# DC-link.net
KiCad netlist of a schematic drawn in Altium Designer
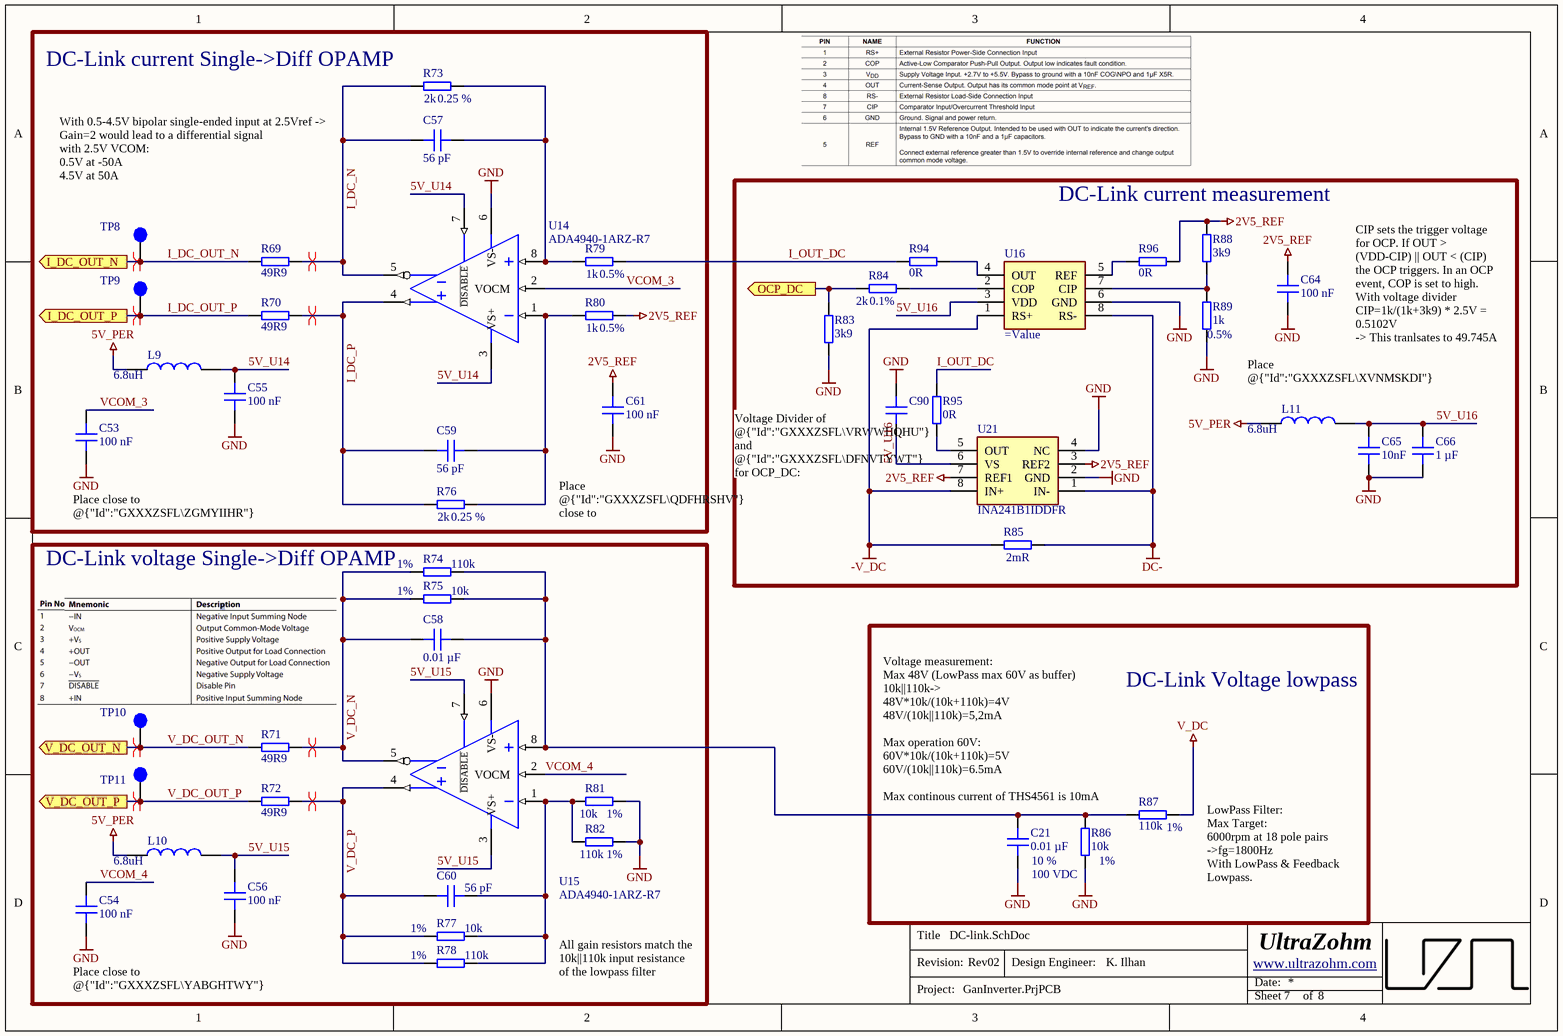
[diagram p0: DC-link.SchDoc]

(export (version "E")
  (design (tool "Eeschema 10.0.6"))
  (components
    (comp (ref "C21")
      (value "0.01 µF")
      (footprint "C_0805")
      (description "100V 10nF 0805 Multilayer Ceramic Capacitors MLCC - SMD/SMT ROHS")
      (fields
        (field (name "MANUFACTURER PART NUMBER") "HV0805X7R103K101NT")
        (field (name "MANUFACTURER") "AIDE")
        (field (name "TOLERANCE") "10 %")
        (field (name "VOLTAGE RATING") "100 VDC")
        (field (name "CREATED FROM") "KIlhan")
      )
      (libsource (lib "user") (part "Capacitor"))
    )
    (comp (ref "C53")
      (value "100 nF")
      (footprint "C_0603")
      (description "Capacitor 0603, 50 VDC, 100 nF, X7R")
      (fields
        (field (name "MANUFACTURER PART NUMBER") "CC0603KRX7R9BB104")
        (field (name "MANUFACTURER") "YAGEO")
        (field (name "CREATED FROM") "AGeiger")
      )
      (libsource (lib "user") (part "Capacitor"))
    )
    (comp (ref "C54")
      (value "100 nF")
      (footprint "C_0603")
      (description "Capacitor 0603, 50 VDC, 100 nF, X7R")
      (fields
        (field (name "MANUFACTURER PART NUMBER") "CC0603KRX7R9BB104")
        (field (name "MANUFACTURER") "YAGEO")
        (field (name "CREATED FROM") "AGeiger")
      )
      (libsource (lib "user") (part "Capacitor"))
    )
    (comp (ref "C55")
      (value "100 nF")
      (footprint "C_0603")
      (description "Capacitor 0603, 50 VDC, 100 nF, X7R")
      (fields
        (field (name "MANUFACTURER PART NUMBER") "CC0603KRX7R9BB104")
        (field (name "MANUFACTURER") "YAGEO")
        (field (name "CREATED FROM") "AGeiger")
      )
      (libsource (lib "user") (part "Capacitor"))
    )
    (comp (ref "C56")
      (value "100 nF")
      (footprint "C_0603")
      (description "Capacitor 0603, 50 VDC, 100 nF, X7R")
      (fields
        (field (name "MANUFACTURER PART NUMBER") "CC0603KRX7R9BB104")
        (field (name "MANUFACTURER") "YAGEO")
        (field (name "CREATED FROM") "AGeiger")
      )
      (libsource (lib "user") (part "Capacitor"))
    )
    (comp (ref "C57")
      (value "56 pF")
      (footprint "C_0603")
      (description "Capacitor 0603, 50 VDC, 56 pF, C0G")
      (fields
        (field (name "MANUFACTURER PART NUMBER") "CL10C560JB8NNNC")
        (field (name "MANUFACTURER") "Samsung Electro-Mechanics")
        (field (name "CREATED FROM") "DHufnagel")
      )
      (libsource (lib "user") (part "Capacitor"))
    )
    (comp (ref "C58")
      (value "0.01 µF")
      (footprint "C_0603")
      (description "25V 10nF C0G ±5% 0603 Multilayer Ceramic Capacitors MLCC - SMD/SMT ROHS")
      (fields
        (field (name "MANUFACTURER PART NUMBER") "C1608C0G1E103JT000N")
        (field (name "MANUFACTURER") "TDK")
        (field (name "CREATED FROM") "KIlhan")
      )
      (libsource (lib "user") (part "Capacitor"))
    )
    (comp (ref "C59")
      (value "56 pF")
      (footprint "C_0603")
      (description "Capacitor 0603, 50 VDC, 56 pF, C0G")
      (fields
        (field (name "MANUFACTURER PART NUMBER") "CL10C560JB8NNNC")
        (field (name "MANUFACTURER") "Samsung Electro-Mechanics")
        (field (name "CREATED FROM") "DHufnagel")
      )
      (libsource (lib "user") (part "Capacitor"))
    )
    (comp (ref "C60")
      (value "56 pF")
      (footprint "C_0603")
      (description "Capacitor 0603, 50 VDC, 56 pF, C0G")
      (fields
        (field (name "MANUFACTURER PART NUMBER") "CL10C560JB8NNNC")
        (field (name "MANUFACTURER") "Samsung Electro-Mechanics")
        (field (name "CREATED FROM") "DHufnagel")
      )
      (libsource (lib "user") (part "Capacitor"))
    )
    (comp (ref "C61")
      (value "100 nF")
      (footprint "C_0603")
      (description "Capacitor 0603, 50 VDC, 100 nF, X7R")
      (fields
        (field (name "MANUFACTURER PART NUMBER") "CC0603KRX7R9BB104")
        (field (name "MANUFACTURER") "YAGEO")
        (field (name "CREATED FROM") "AGeiger")
      )
      (libsource (lib "user") (part "Capacitor"))
    )
    (comp (ref "C64")
      (value "100 nF")
      (footprint "C_0603")
      (description "Capacitor 0603, 50 VDC, 100 nF, X7R")
      (fields
        (field (name "MANUFACTURER PART NUMBER") "CC0603KRX7R9BB104")
        (field (name "MANUFACTURER") "YAGEO")
        (field (name "CREATED FROM") "AGeiger")
      )
      (libsource (lib "user") (part "Capacitor"))
    )
    (comp (ref "C65")
      (value "10nF")
      (footprint "C_0603")
      (description "50V 10nF 2X1 ±10%")
      (fields
        (field (name "MANUFACTURER PART NUMBER") "CT41G-0603-2X1-50V-0.01μF-K(N)")
        (field (name "MANUFACTURER") "TORCH")
        (field (name "CREATED FROM") "KIlhan")
      )
      (libsource (lib "user") (part "Capacitor"))
    )
    (comp (ref "C66")
      (value "1 µF")
      (footprint "C_0603")
      (description "50V 1uF X7R ±10% 0603 Multilayer Ceramic Capacitors MLCC - SMD/SMT ROHS")
      (fields
        (field (name "MANUFACTURER PART NUMBER") "UMK107AB7105KA-T")
        (field (name "MANUFACTURER") "Taiyo Yuden")
        (field (name "CREATED FROM") "NDiringer")
      )
      (libsource (lib "user") (part "Capacitor"))
    )
    (comp (ref "C90")
      (value "100 nF")
      (footprint "C_0603")
      (description "Capacitor 0603, 50 VDC, 100 nF, X7R")
      (fields
        (field (name "MANUFACTURER PART NUMBER") "CC0603KRX7R9BB104")
        (field (name "MANUFACTURER") "YAGEO")
        (field (name "CREATED FROM") "AGeiger")
      )
      (libsource (lib "user") (part "Capacitor"))
    )
    (comp (ref "L9")
      (value "6.8uH")
      (footprint "INDC1608X95N")
      (description "6.8uH ±10% 0603 Inductors (SMD) ROHS")
      (fields
        (field (name "MF") "EPCOS / TDK")
        (field (name "MPN") "B82464G4154M")
        (field (name "CREATED FROM") "KIlhan")
      )
      (libsource (lib "user") (part "B82464G4154M"))
    )
    (comp (ref "L10")
      (value "6.8uH")
      (footprint "INDC1608X95N")
      (description "6.8uH ±10% 0603 Inductors (SMD) ROHS")
      (fields
        (field (name "MF") "EPCOS / TDK")
        (field (name "MPN") "B82464G4154M")
        (field (name "CREATED FROM") "KIlhan")
      )
      (libsource (lib "user") (part "B82464G4154M"))
    )
    (comp (ref "L11")
      (value "6.8uH")
      (footprint "INDC1608X95N")
      (description "6.8uH ±10% 0603 Inductors (SMD) ROHS")
      (fields
        (field (name "MF") "EPCOS / TDK")
        (field (name "MPN") "B82464G4154M")
        (field (name "CREATED FROM") "KIlhan")
      )
      (libsource (lib "user") (part "B82464G4154M"))
    )
    (comp (ref "R69")
      (value "49R9")
      (footprint "RES 0603_1608")
      (description "125mW Thin Film Resistor ±0.1% ±25ppm/℃ 49.9Ω 0603")
      (fields
        (field (name "MANUFACTURER PART NUMBER") "TNPW060349R9BEEA")
        (field (name "MANUFACTURER") "Vishay Intertech")
        (field (name "CREATED FROM") "KIlhan")
      )
      (libsource (lib "user") (part "Resistor"))
    )
    (comp (ref "R70")
      (value "49R9")
      (footprint "RES 0603_1608")
      (description "125mW Thin Film Resistor ±0.1% ±25ppm/℃ 49.9Ω 0603")
      (fields
        (field (name "MANUFACTURER PART NUMBER") "TNPW060349R9BEEA")
        (field (name "MANUFACTURER") "Vishay Intertech")
        (field (name "CREATED FROM") "KIlhan")
      )
      (libsource (lib "user") (part "Resistor"))
    )
    (comp (ref "R71")
      (value "49R9")
      (footprint "RES 0603_1608")
      (description "125mW Thin Film Resistor ±0.1% ±25ppm/℃ 49.9Ω 0603")
      (fields
        (field (name "MANUFACTURER PART NUMBER") "TNPW060349R9BEEA")
        (field (name "MANUFACTURER") "Vishay Intertech")
        (field (name "CREATED FROM") "KIlhan")
      )
      (libsource (lib "user") (part "Resistor"))
    )
    (comp (ref "R72")
      (value "49R9")
      (footprint "RES 0603_1608")
      (description "125mW Thin Film Resistor ±0.1% ±25ppm/℃ 49.9Ω 0603")
      (fields
        (field (name "MANUFACTURER PART NUMBER") "TNPW060349R9BEEA")
        (field (name "MANUFACTURER") "Vishay Intertech")
        (field (name "CREATED FROM") "KIlhan")
      )
      (libsource (lib "user") (part "Resistor"))
    )
    (comp (ref "R73")
      (value "2k")
      (footprint "RES 0603_1608")
      (description "100mW Thin Film Resistor ±50ppm/℃ ±0.25% 2kΩ 0603 Chip Resistor - Surface Mount ROHS")
      (fields
        (field (name "MANUFACTURER PART NUMBER") "RT0603CRE072KL")
        (field (name "MANUFACTURER") "YAGEO")
        (field (name "TOLERANCE") "0.25 %")
        (field (name "CREATED FROM") "KIlhan")
      )
      (libsource (lib "user") (part "Resistor"))
    )
    (comp (ref "R74")
      (value "110k")
      (footprint "RES 0603_1608")
      (description "100mW Thick Film Resistors ±100ppm/℃ ±1% 110kΩ 0603 Chip Resistor - Surface Mount ROHS")
      (fields
        (field (name "MANUFACTURER PART NUMBER") "WR06X1103FTL")
        (field (name "MANUFACTURER") "Walsin Tech Corp")
        (field (name "TOLERANCE") "1%")
        (field (name "CREATED FROM") "KIlhan")
      )
      (libsource (lib "user") (part "Resistor"))
    )
    (comp (ref "R75")
      (value "10k")
      (footprint "RES 0603_1608")
      (description "SMD resistor 1%")
      (fields
        (field (name "MANUFACTURER PART NUMBER") "0603WAF1002T5E")
        (field (name "MANUFACTURER") "UNI-ROYAL")
        (field (name "TOLERANCE") "1%")
        (field (name "CREATED FROM") "AGeiger")
      )
      (libsource (lib "user") (part "Resistor"))
    )
    (comp (ref "R76")
      (value "2k")
      (footprint "RES 0603_1608")
      (description "100mW Thin Film Resistor ±50ppm/℃ ±0.25% 2kΩ 0603 Chip Resistor - Surface Mount ROHS")
      (fields
        (field (name "MANUFACTURER PART NUMBER") "RT0603CRE072KL")
        (field (name "MANUFACTURER") "YAGEO")
        (field (name "TOLERANCE") "0.25 %")
        (field (name "CREATED FROM") "KIlhan")
      )
      (libsource (lib "user") (part "Resistor"))
    )
    (comp (ref "R77")
      (value "10k")
      (footprint "RES 0603_1608")
      (description "SMD resistor 1%")
      (fields
        (field (name "MANUFACTURER PART NUMBER") "0603WAF1002T5E")
        (field (name "MANUFACTURER") "UNI-ROYAL")
        (field (name "TOLERANCE") "1%")
        (field (name "CREATED FROM") "AGeiger")
      )
      (libsource (lib "user") (part "Resistor"))
    )
    (comp (ref "R78")
      (value "110k")
      (footprint "RES 0603_1608")
      (description "100mW Thick Film Resistors ±100ppm/℃ ±1% 110kΩ 0603 Chip Resistor - Surface Mount ROHS")
      (fields
        (field (name "MANUFACTURER PART NUMBER") "WR06X1103FTL")
        (field (name "MANUFACTURER") "Walsin Tech Corp")
        (field (name "TOLERANCE") "1%")
        (field (name "CREATED FROM") "KIlhan")
      )
      (libsource (lib "user") (part "Resistor"))
    )
    (comp (ref "R79")
      (value "1k")
      (footprint "RES 0603_1608")
      (description "SMD resistor E24 series 470 kOhms 100-200 mW 0603 1%")
      (fields
        (field (name "MANUFACTURER PART NUMBER") "0603WAD1001T5E")
        (field (name "MANUFACTURER") "UNI-ROYAL(Uniroyal Elec)")
        (field (name "TOLERANCE") "0.5%")
        (field (name "CREATED FROM") "NDiringer")
      )
      (libsource (lib "user") (part "Resistor"))
    )
    (comp (ref "R80")
      (value "1k")
      (footprint "RES 0603_1608")
      (description "SMD resistor E24 series 470 kOhms 100-200 mW 0603 1%")
      (fields
        (field (name "MANUFACTURER PART NUMBER") "0603WAD1001T5E")
        (field (name "MANUFACTURER") "UNI-ROYAL(Uniroyal Elec)")
        (field (name "TOLERANCE") "0.5%")
        (field (name "CREATED FROM") "NDiringer")
      )
      (libsource (lib "user") (part "Resistor"))
    )
    (comp (ref "R81")
      (value "10k")
      (footprint "RES 0603_1608")
      (description "SMD resistor 1%")
      (fields
        (field (name "MANUFACTURER PART NUMBER") "0603WAF1002T5E")
        (field (name "MANUFACTURER") "UNI-ROYAL")
        (field (name "TOLERANCE") "1%")
        (field (name "CREATED FROM") "AGeiger")
      )
      (libsource (lib "user") (part "Resistor"))
    )
    (comp (ref "R82")
      (value "110k")
      (footprint "RES 0603_1608")
      (description "100mW Thick Film Resistors ±100ppm/℃ ±1% 110kΩ 0603 Chip Resistor - Surface Mount ROHS")
      (fields
        (field (name "MANUFACTURER PART NUMBER") "WR06X1103FTL")
        (field (name "MANUFACTURER") "Walsin Tech Corp")
        (field (name "TOLERANCE") "1%")
        (field (name "CREATED FROM") "KIlhan")
      )
      (libsource (lib "user") (part "Resistor"))
    )
    (comp (ref "R83")
      (value "3k9")
      (footprint "RES 0603_1608")
      (description "SMD resistor E24 series")
      (fields
        (field (name "MANUFACTURER PART NUMBER") "RT0603FRE073K9L")
        (field (name "MANUFACTURER") "YAGEO")
        (field (name "CREATED FROM") "DHufnagel")
      )
      (libsource (lib "user") (part "Resistor"))
    )
    (comp (ref "R84")
      (value "2k")
      (footprint "RES 0603_1608")
      (description "SMD resistor 0.1%")
      (fields
        (field (name "MANUFACTURER PART NUMBER") "ERJ-PB3B2001V")
        (field (name "MANUFACTURER") "Panasonic")
        (field (name "TOLERANCE") "0.1%")
        (field (name "CREATED FROM") "DHufnagel")
      )
      (libsource (lib "user") (part "Resistor"))
    )
    (comp (ref "R85")
      (value "2mR")
      (footprint "3921")
      (description "Shunt resistor 2mOhm, 5W, 1%")
      (fields
        (field (name "MANUFACTURER PART NUMBER") "PU3921FKMP50R002L")
        (field (name "MANUFACTURER") "YAGEO")
        (field (name "CREATED FROM") "DHufnagel")
      )
      (libsource (lib "user") (part "Resistor"))
    )
    (comp (ref "R86")
      (value "10k")
      (footprint "RES 0603_1608")
      (description "SMD resistor 1%")
      (fields
        (field (name "MANUFACTURER PART NUMBER") "0603WAF1002T5E")
        (field (name "MANUFACTURER") "UNI-ROYAL")
        (field (name "TOLERANCE") "1%")
        (field (name "CREATED FROM") "AGeiger")
      )
      (libsource (lib "user") (part "Resistor"))
    )
    (comp (ref "R87")
      (value "110k")
      (footprint "RES 0603_1608")
      (description "100mW Thick Film Resistors ±100ppm/℃ ±1% 110kΩ 0603 Chip Resistor - Surface Mount ROHS")
      (fields
        (field (name "MANUFACTURER PART NUMBER") "WR06X1103FTL")
        (field (name "MANUFACTURER") "Walsin Tech Corp")
        (field (name "TOLERANCE") "1%")
        (field (name "CREATED FROM") "KIlhan")
      )
      (libsource (lib "user") (part "Resistor"))
    )
    (comp (ref "R88")
      (value "3k9")
      (footprint "RES 0603_1608")
      (description "SMD resistor E24 series")
      (fields
        (field (name "MANUFACTURER PART NUMBER") "RT0603FRE073K9L")
        (field (name "MANUFACTURER") "YAGEO")
        (field (name "CREATED FROM") "DHufnagel")
      )
      (libsource (lib "user") (part "Resistor"))
    )
    (comp (ref "R89")
      (value "1k")
      (footprint "RES 0603_1608")
      (description "SMD resistor E24 series 470 kOhms 100-200 mW 0603 1%")
      (fields
        (field (name "MANUFACTURER PART NUMBER") "0603WAD1001T5E")
        (field (name "MANUFACTURER") "UNI-ROYAL(Uniroyal Elec)")
        (field (name "TOLERANCE") "0.5%")
        (field (name "CREATED FROM") "NDiringer")
      )
      (libsource (lib "user") (part "Resistor"))
    )
    (comp (ref "R94")
      (value "0R")
      (footprint "RES 0603_1608")
      (description "SMD resistor E24 series")
      (fields
        (field (name "MANUFACTURER PART NUMBER") "RC0603JR-070RL")
        (field (name "MANUFACTURER") "YAGEO")
        (field (name "CREATED FROM") "MGremer")
      )
      (libsource (lib "user") (part "Resistor"))
    )
    (comp (ref "R95")
      (value "0R")
      (footprint "RES 0603_1608")
      (description "SMD resistor E24 series")
      (fields
        (field (name "MANUFACTURER PART NUMBER") "RC0603JR-070RL")
        (field (name "MANUFACTURER") "YAGEO")
        (field (name "CREATED FROM") "MGremer")
      )
      (libsource (lib "user") (part "Resistor"))
    )
    (comp (ref "R96")
      (value "0R")
      (footprint "RES 0603_1608")
      (description "SMD resistor E24 series")
      (fields
        (field (name "MANUFACTURER PART NUMBER") "RC0603JR-070RL")
        (field (name "MANUFACTURER") "YAGEO")
        (field (name "CREATED FROM") "MGremer")
      )
      (libsource (lib "user") (part "Resistor"))
    )
    (comp (ref "TP8")
      (value "Testpoint 1mm")
      (footprint "TP_1mm")
      (fields
        (field (name "MANUFACTURER PART NUMBER") "NULL")
        (field (name "CREATED") "2018_06_25_AGeiger")
        (field (name "CREATED FROM") "AGeiger")
      )
      (libsource (lib "user") (part "TP_1mm"))
    )
    (comp (ref "TP9")
      (value "Testpoint 1mm")
      (footprint "TP_1mm")
      (fields
        (field (name "MANUFACTURER PART NUMBER") "NULL")
        (field (name "CREATED") "2018_06_25_AGeiger")
        (field (name "CREATED FROM") "AGeiger")
      )
      (libsource (lib "user") (part "TP_1mm"))
    )
    (comp (ref "TP10")
      (value "Testpoint 1mm")
      (footprint "TP_1mm")
      (fields
        (field (name "MANUFACTURER PART NUMBER") "NULL")
        (field (name "CREATED") "2018_06_25_AGeiger")
        (field (name "CREATED FROM") "AGeiger")
      )
      (libsource (lib "user") (part "TP_1mm"))
    )
    (comp (ref "TP11")
      (value "Testpoint 1mm")
      (footprint "TP_1mm")
      (fields
        (field (name "MANUFACTURER PART NUMBER") "NULL")
        (field (name "CREATED") "2018_06_25_AGeiger")
        (field (name "CREATED FROM") "AGeiger")
      )
      (libsource (lib "user") (part "TP_1mm"))
    )
    (comp (ref "U14")
      (value "ADA4940-1ARZ-R7")
      (footprint "SOT127P600X175-8N")
      (description "Fully Differential Amplifier, Ultralow-Power,Low Distortion, 260-MHz")
      (fields
        (field (name "MANUFACTURER") "Analog Devices")
        (field (name "LCSC PART NUMBER") "C730049")
        (field (name "CREATED FROM") "DHufnagel")
      )
      (libsource (lib "user") (part "ADA4940-1ARZ"))
    )
    (comp (ref "U15")
      (value "ADA4940-1ARZ-R7")
      (footprint "SOT127P600X175-8N")
      (description "Fully Differential Amplifier, Ultralow-Power,Low Distortion, 260-MHz")
      (fields
        (field (name "MANUFACTURER") "Analog Devices")
        (field (name "LCSC PART NUMBER") "C730049")
        (field (name "CREATED FROM") "DHufnagel")
      )
      (libsource (lib "user") (part "ADA4940-1ARZ"))
    )
    (comp (ref "U16")
      (value "~")
      (footprint "SOP65P490X110-8N")
      (description "Current Sense Amplifier, 300kHz, -0.1V to 65V CMV, 2 Channel")
      (fields
        (field (name "MANUFACTURER_PART_NUMBER") "MAX40056TAUA+")
        (field (name "MOUSER PART NUMBER") "700-MAX40056TAUA+")
        (field (name "CREATED FROM") "KIlhan")
      )
      (libsource (lib "user") (part "MAX40056TAUA+"))
    )
    (comp (ref "U21")
      (value "INA241B1IDDFR")
      (footprint "SOT65P280X110-8N")
      (fields
        (field (name "MOUSER PART NUMBER") "595-INA241B1IDDFR")
        (field (name "LCSC PART NUMBER") "C7433256")
        (field (name "MANUFACTURER") "Texas Instruments")
        (field (name "CREATED FROM") "KIlhan")
      )
      (libsource (lib "user") (part "INA241B1IDDFR"))
    )
  )
  (nets
    (net (code "1") (name "-V_DC") (class "Default")
      (node (ref "R85") (pin "1") (pinfunction "1_1") (pintype "passive"))
      (node (ref "U16") (pin "1") (pinfunction "RS+_1") (pintype "passive"))
      (node (ref "U21") (pin "8") (pinfunction "IN+_8") (pintype "passive"))
    )
    (net (code "2") (name "/5V_U14") (class "Default")
      (node (ref "C55") (pin "2") (pinfunction "2_2") (pintype "passive"))
      (node (ref "L9") (pin "2") (pinfunction "2_2") (pintype "passive"))
      (node (ref "U14") (pin "3") (pinfunction "VS+_3") (pintype "power_in"))
      (node (ref "U14") (pin "7") (pinfunction "~{DISABLE}_7") (pintype "input"))
    )
    (net (code "3") (name "/5V_U15") (class "Default")
      (node (ref "C56") (pin "2") (pinfunction "2_2") (pintype "passive"))
      (node (ref "L10") (pin "2") (pinfunction "2_2") (pintype "passive"))
      (node (ref "U15") (pin "3") (pinfunction "VS+_3") (pintype "power_in"))
      (node (ref "U15") (pin "7") (pinfunction "~{DISABLE}_7") (pintype "input"))
    )
    (net (code "4") (name "/5V_U16") (class "Default")
      (node (ref "C65") (pin "2") (pinfunction "2_2") (pintype "passive"))
      (node (ref "C66") (pin "2") (pinfunction "2_2") (pintype "passive"))
      (node (ref "C90") (pin "2") (pinfunction "2_2") (pintype "passive"))
      (node (ref "L11") (pin "2") (pinfunction "2_2") (pintype "passive"))
      (node (ref "U16") (pin "3") (pinfunction "VDD_3") (pintype "passive"))
      (node (ref "U21") (pin "6") (pinfunction "VS_6") (pintype "passive"))
    )
    (net (code "5") (name "/I_DC_N") (class "Default")
      (node (ref "C57") (pin "1") (pinfunction "1_1") (pintype "passive"))
      (node (ref "R69") (pin "2") (pinfunction "2_2") (pintype "passive"))
      (node (ref "R73") (pin "1") (pinfunction "1_1") (pintype "passive"))
      (node (ref "U14") (pin "5") (pinfunction "VOUT-_5") (pintype "output"))
    )
    (net (code "6") (name "/I_DC_OUT_N") (class "Default")
      (node (ref "R69") (pin "1") (pinfunction "1_1") (pintype "passive"))
      (node (ref "TP8") (pin "1") (pintype "passive"))
    )
    (net (code "7") (name "/I_DC_OUT_P") (class "Default")
      (node (ref "R70") (pin "1") (pinfunction "1_1") (pintype "passive"))
      (node (ref "TP9") (pin "1") (pintype "passive"))
    )
    (net (code "8") (name "/I_DC_P") (class "Default")
      (node (ref "C59") (pin "2") (pinfunction "2_2") (pintype "passive"))
      (node (ref "R70") (pin "2") (pinfunction "2_2") (pintype "passive"))
      (node (ref "R76") (pin "2") (pinfunction "2_2") (pintype "passive"))
      (node (ref "U14") (pin "4") (pinfunction "VOUT+_4") (pintype "output"))
    )
    (net (code "9") (name "/I_OUT_DC") (class "Default")
      (node (ref "R79") (pin "2") (pinfunction "2_2") (pintype "passive"))
      (node (ref "R94") (pin "1") (pinfunction "1_1") (pintype "passive"))
      (node (ref "R95") (pin "2") (pinfunction "2_2") (pintype "passive"))
    )
    (net (code "10") (name "/OCP_DC") (class "Default")
      (node (ref "R83") (pin "2") (pinfunction "2_2") (pintype "passive"))
      (node (ref "R84") (pin "2") (pinfunction "2_2") (pintype "passive"))
    )
    (net (code "11") (name "/VCOM_3") (class "Default")
      (node (ref "C53") (pin "2") (pinfunction "2_2") (pintype "passive"))
      (node (ref "U14") (pin "2") (pinfunction "VOCM_2") (pintype "input"))
    )
    (net (code "12") (name "/VCOM_4") (class "Default")
      (node (ref "C54") (pin "2") (pinfunction "2_2") (pintype "passive"))
      (node (ref "U15") (pin "2") (pinfunction "VOCM_2") (pintype "input"))
    )
    (net (code "13") (name "/V_DC_N") (class "Default")
      (node (ref "C58") (pin "1") (pinfunction "1_1") (pintype "passive"))
      (node (ref "R71") (pin "2") (pinfunction "2_2") (pintype "passive"))
      (node (ref "R74") (pin "1") (pinfunction "1_1") (pintype "passive"))
      (node (ref "R75") (pin "2") (pinfunction "2_2") (pintype "passive"))
      (node (ref "U15") (pin "5") (pinfunction "VOUT-_5") (pintype "output"))
    )
    (net (code "14") (name "/V_DC_OUT_N") (class "Default")
      (node (ref "R71") (pin "1") (pinfunction "1_1") (pintype "passive"))
      (node (ref "TP10") (pin "1") (pintype "passive"))
    )
    (net (code "15") (name "/V_DC_OUT_P") (class "Default")
      (node (ref "R72") (pin "1") (pinfunction "1_1") (pintype "passive"))
      (node (ref "TP11") (pin "1") (pintype "passive"))
    )
    (net (code "16") (name "/V_DC_P") (class "Default")
      (node (ref "C60") (pin "2") (pinfunction "2_2") (pintype "passive"))
      (node (ref "R72") (pin "2") (pinfunction "2_2") (pintype "passive"))
      (node (ref "R77") (pin "2") (pinfunction "2_2") (pintype "passive"))
      (node (ref "R78") (pin "1") (pinfunction "1_1") (pintype "passive"))
      (node (ref "U15") (pin "4") (pinfunction "VOUT+_4") (pintype "output"))
    )
    (net (code "17") (name "2V5_REF") (class "Default")
      (node (ref "C61") (pin "1") (pinfunction "1_1") (pintype "passive"))
      (node (ref "C64") (pin "1") (pinfunction "1_1") (pintype "passive"))
      (node (ref "R80") (pin "2") (pinfunction "2_2") (pintype "passive"))
      (node (ref "R88") (pin "2") (pinfunction "2_2") (pintype "passive"))
      (node (ref "R96") (pin "2") (pinfunction "2_2") (pintype "passive"))
      (node (ref "U21") (pin "3") (pinfunction "REF2_3") (pintype "passive"))
      (node (ref "U21") (pin "7") (pinfunction "REF1_7") (pintype "passive"))
    )
    (net (code "18") (name "5V_PER") (class "Default")
      (node (ref "L10") (pin "1") (pinfunction "1_1") (pintype "passive"))
      (node (ref "L11") (pin "1") (pinfunction "1_1") (pintype "passive"))
      (node (ref "L9") (pin "1") (pinfunction "1_1") (pintype "passive"))
    )
    (net (code "19") (name "DC-") (class "Default")
      (node (ref "R85") (pin "2") (pinfunction "2_2") (pintype "passive"))
      (node (ref "U16") (pin "8") (pinfunction "RS-_8") (pintype "passive"))
      (node (ref "U21") (pin "1") (pinfunction "IN-_1") (pintype "passive"))
    )
    (net (code "20") (name "GND") (class "Default")
      (node (ref "C21") (pin "1") (pinfunction "1_1") (pintype "passive"))
      (node (ref "C53") (pin "1") (pinfunction "1_1") (pintype "passive"))
      (node (ref "C54") (pin "1") (pinfunction "1_1") (pintype "passive"))
      (node (ref "C55") (pin "1") (pinfunction "1_1") (pintype "passive"))
      (node (ref "C56") (pin "1") (pinfunction "1_1") (pintype "passive"))
      (node (ref "C61") (pin "2") (pinfunction "2_2") (pintype "passive"))
      (node (ref "C64") (pin "2") (pinfunction "2_2") (pintype "passive"))
      (node (ref "C65") (pin "1") (pinfunction "1_1") (pintype "passive"))
      (node (ref "C66") (pin "1") (pinfunction "1_1") (pintype "passive"))
      (node (ref "C90") (pin "1") (pinfunction "1_1") (pintype "passive"))
      (node (ref "R81") (pin "1") (pinfunction "1_1") (pintype "passive"))
      (node (ref "R82") (pin "2") (pinfunction "2_2") (pintype "passive"))
      (node (ref "R83") (pin "1") (pinfunction "1_1") (pintype "passive"))
      (node (ref "R86") (pin "1") (pinfunction "1_1") (pintype "passive"))
      (node (ref "R89") (pin "1") (pinfunction "1_1") (pintype "passive"))
      (node (ref "U14") (pin "6") (pinfunction "VS-_6") (pintype "power_in"))
      (node (ref "U15") (pin "6") (pinfunction "VS-_6") (pintype "power_in"))
      (node (ref "U16") (pin "6") (pinfunction "GND_6") (pintype "passive"))
      (node (ref "U21") (pin "2") (pinfunction "GND_2") (pintype "passive"))
      (node (ref "U21") (pin "4") (pinfunction "NC_4") (pintype "passive"))
    )
    (net (code "21") (name "Net-(U14-VIN+)") (class "Default")
      (node (ref "C57") (pin "2") (pinfunction "2_2") (pintype "passive"))
      (node (ref "R73") (pin "2") (pinfunction "2_2") (pintype "passive"))
      (node (ref "R79") (pin "1") (pinfunction "1_1") (pintype "passive"))
      (node (ref "U14") (pin "8") (pinfunction "VIN+_8") (pintype "input"))
    )
    (net (code "22") (name "Net-(U14-VIN-)") (class "Default")
      (node (ref "C59") (pin "1") (pinfunction "1_1") (pintype "passive"))
      (node (ref "R76") (pin "1") (pinfunction "1_1") (pintype "passive"))
      (node (ref "R80") (pin "1") (pinfunction "1_1") (pintype "passive"))
      (node (ref "U14") (pin "1") (pinfunction "VIN-_1") (pintype "input"))
    )
    (net (code "23") (name "Net-(U15-VIN+)") (class "Default")
      (node (ref "C21") (pin "2") (pinfunction "2_2") (pintype "passive"))
      (node (ref "C58") (pin "2") (pinfunction "2_2") (pintype "passive"))
      (node (ref "R74") (pin "2") (pinfunction "2_2") (pintype "passive"))
      (node (ref "R75") (pin "1") (pinfunction "1_1") (pintype "passive"))
      (node (ref "R86") (pin "2") (pinfunction "2_2") (pintype "passive"))
      (node (ref "R87") (pin "1") (pinfunction "1_1") (pintype "passive"))
      (node (ref "U15") (pin "8") (pinfunction "VIN+_8") (pintype "input"))
    )
    (net (code "24") (name "Net-(U15-VIN-)") (class "Default")
      (node (ref "C60") (pin "1") (pinfunction "1_1") (pintype "passive"))
      (node (ref "R77") (pin "1") (pinfunction "1_1") (pintype "passive"))
      (node (ref "R78") (pin "2") (pinfunction "2_2") (pintype "passive"))
      (node (ref "R81") (pin "2") (pinfunction "2_2") (pintype "passive"))
      (node (ref "R82") (pin "1") (pinfunction "1_1") (pintype "passive"))
      (node (ref "U15") (pin "1") (pinfunction "VIN-_1") (pintype "input"))
    )
    (net (code "25") (name "Net-(U16-CIP)") (class "Default")
      (node (ref "R88") (pin "1") (pinfunction "1_1") (pintype "passive"))
      (node (ref "R89") (pin "2") (pinfunction "2_2") (pintype "passive"))
      (node (ref "U16") (pin "7") (pinfunction "CIP_7") (pintype "passive"))
    )
    (net (code "26") (name "Net-(U16-COP)") (class "Default")
      (node (ref "R84") (pin "1") (pinfunction "1_1") (pintype "passive"))
      (node (ref "U16") (pin "2") (pinfunction "COP_2") (pintype "passive"))
    )
    (net (code "27") (name "Net-(U16-OUT)") (class "Default")
      (node (ref "R94") (pin "2") (pinfunction "2_2") (pintype "passive"))
      (node (ref "U16") (pin "4") (pinfunction "OUT_4") (pintype "passive"))
    )
    (net (code "28") (name "Net-(U16-REF)") (class "Default")
      (node (ref "R96") (pin "1") (pinfunction "1_1") (pintype "passive"))
      (node (ref "U16") (pin "5") (pinfunction "REF_5") (pintype "passive"))
    )
    (net (code "29") (name "Net-(U21-OUT)") (class "Default")
      (node (ref "R95") (pin "1") (pinfunction "1_1") (pintype "passive"))
      (node (ref "U21") (pin "5") (pinfunction "OUT_5") (pintype "passive"))
    )
    (net (code "30") (name "V_DC") (class "Default")
      (node (ref "R87") (pin "2") (pinfunction "2_2") (pintype "passive"))
    )
  )
)
